# Sheet1.net
KiCad netlist of a schematic drawn in Altium Designer
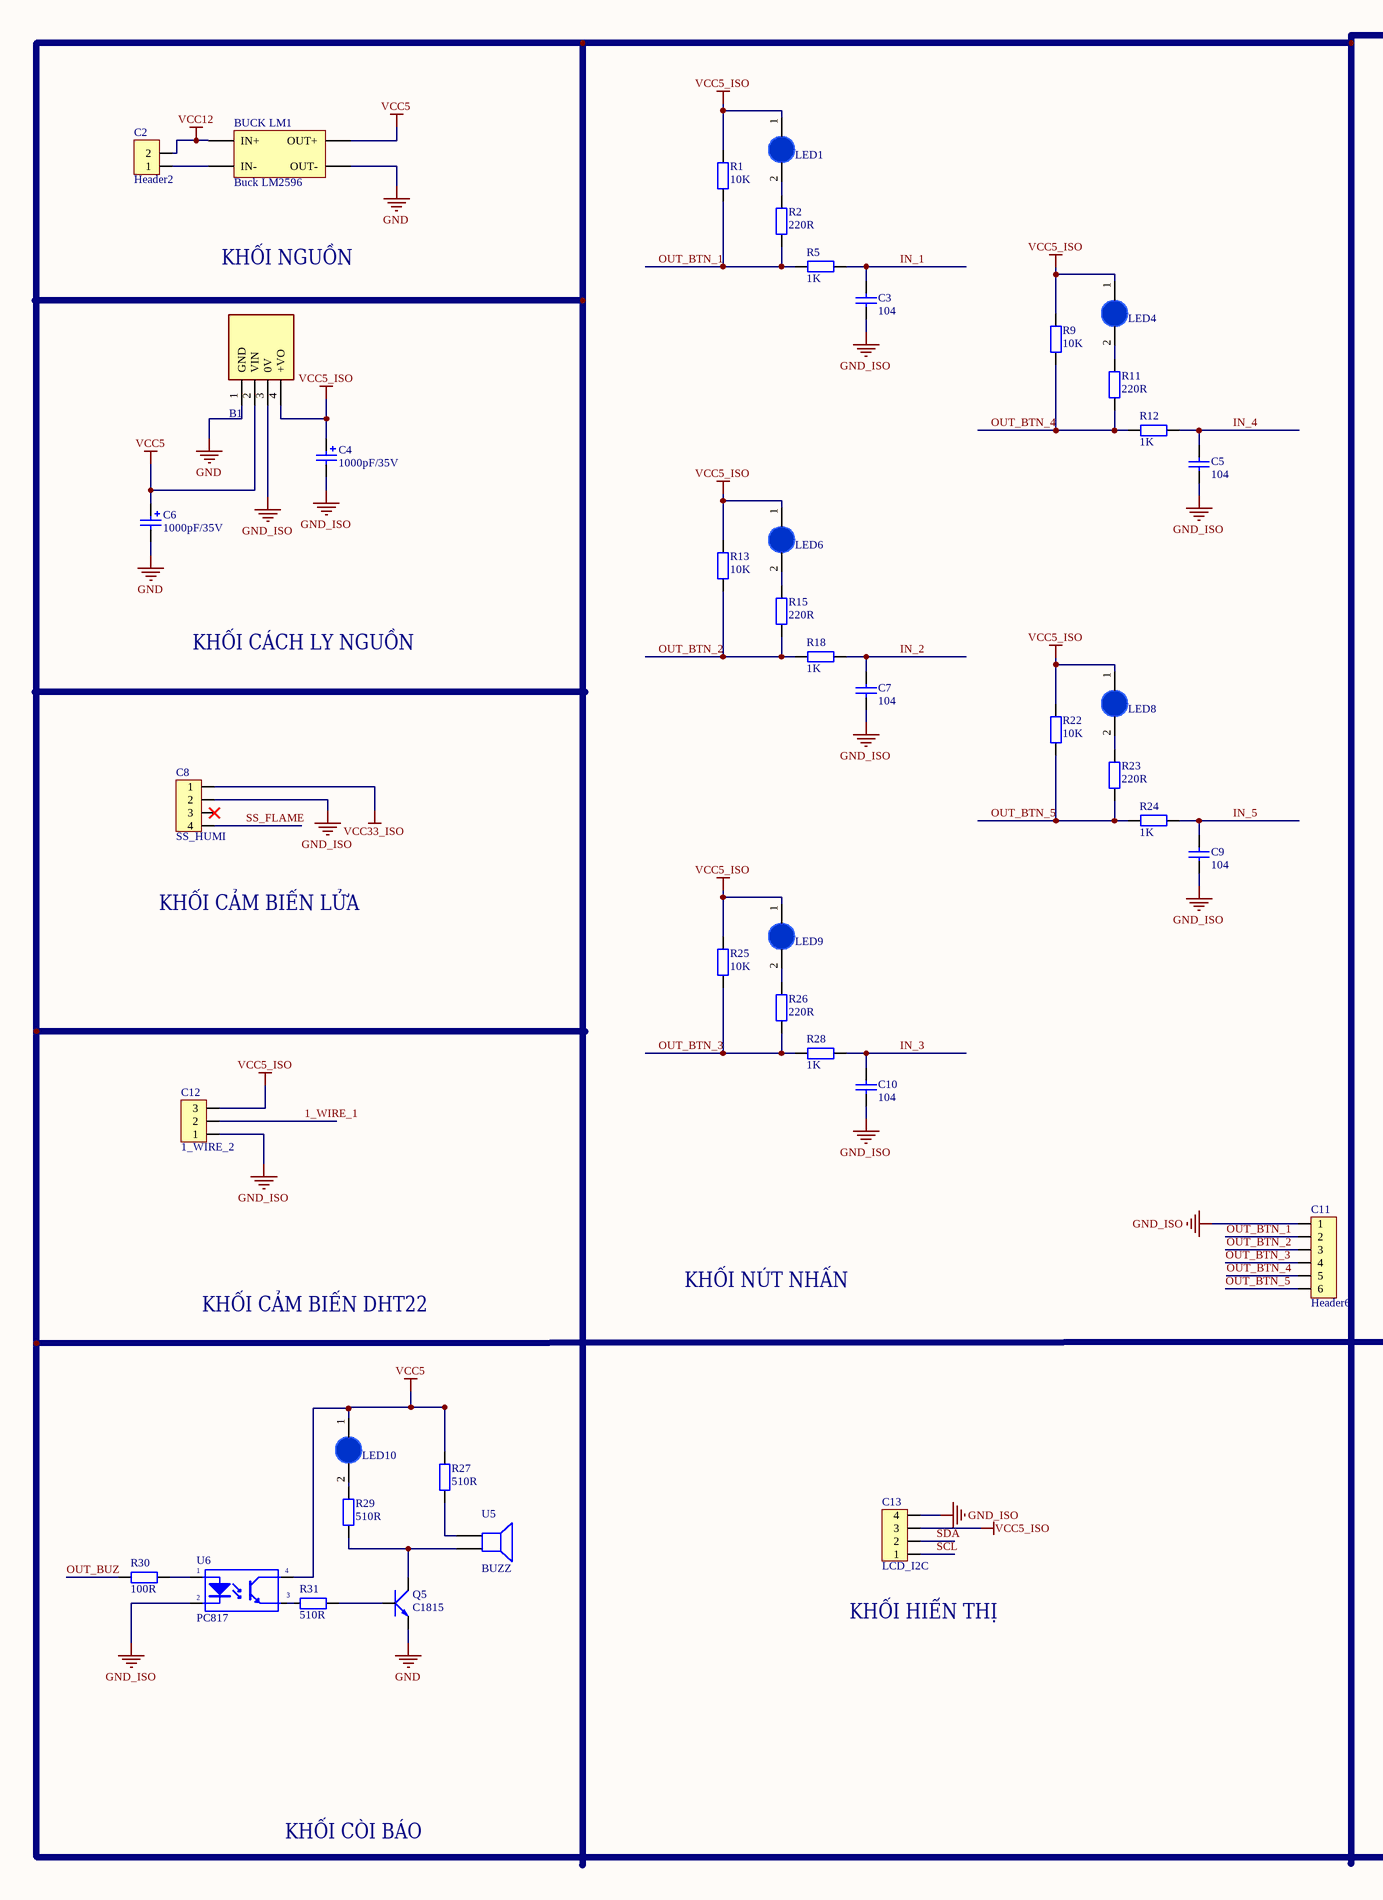
[diagram p0: Sheet1.SchDoc, left]
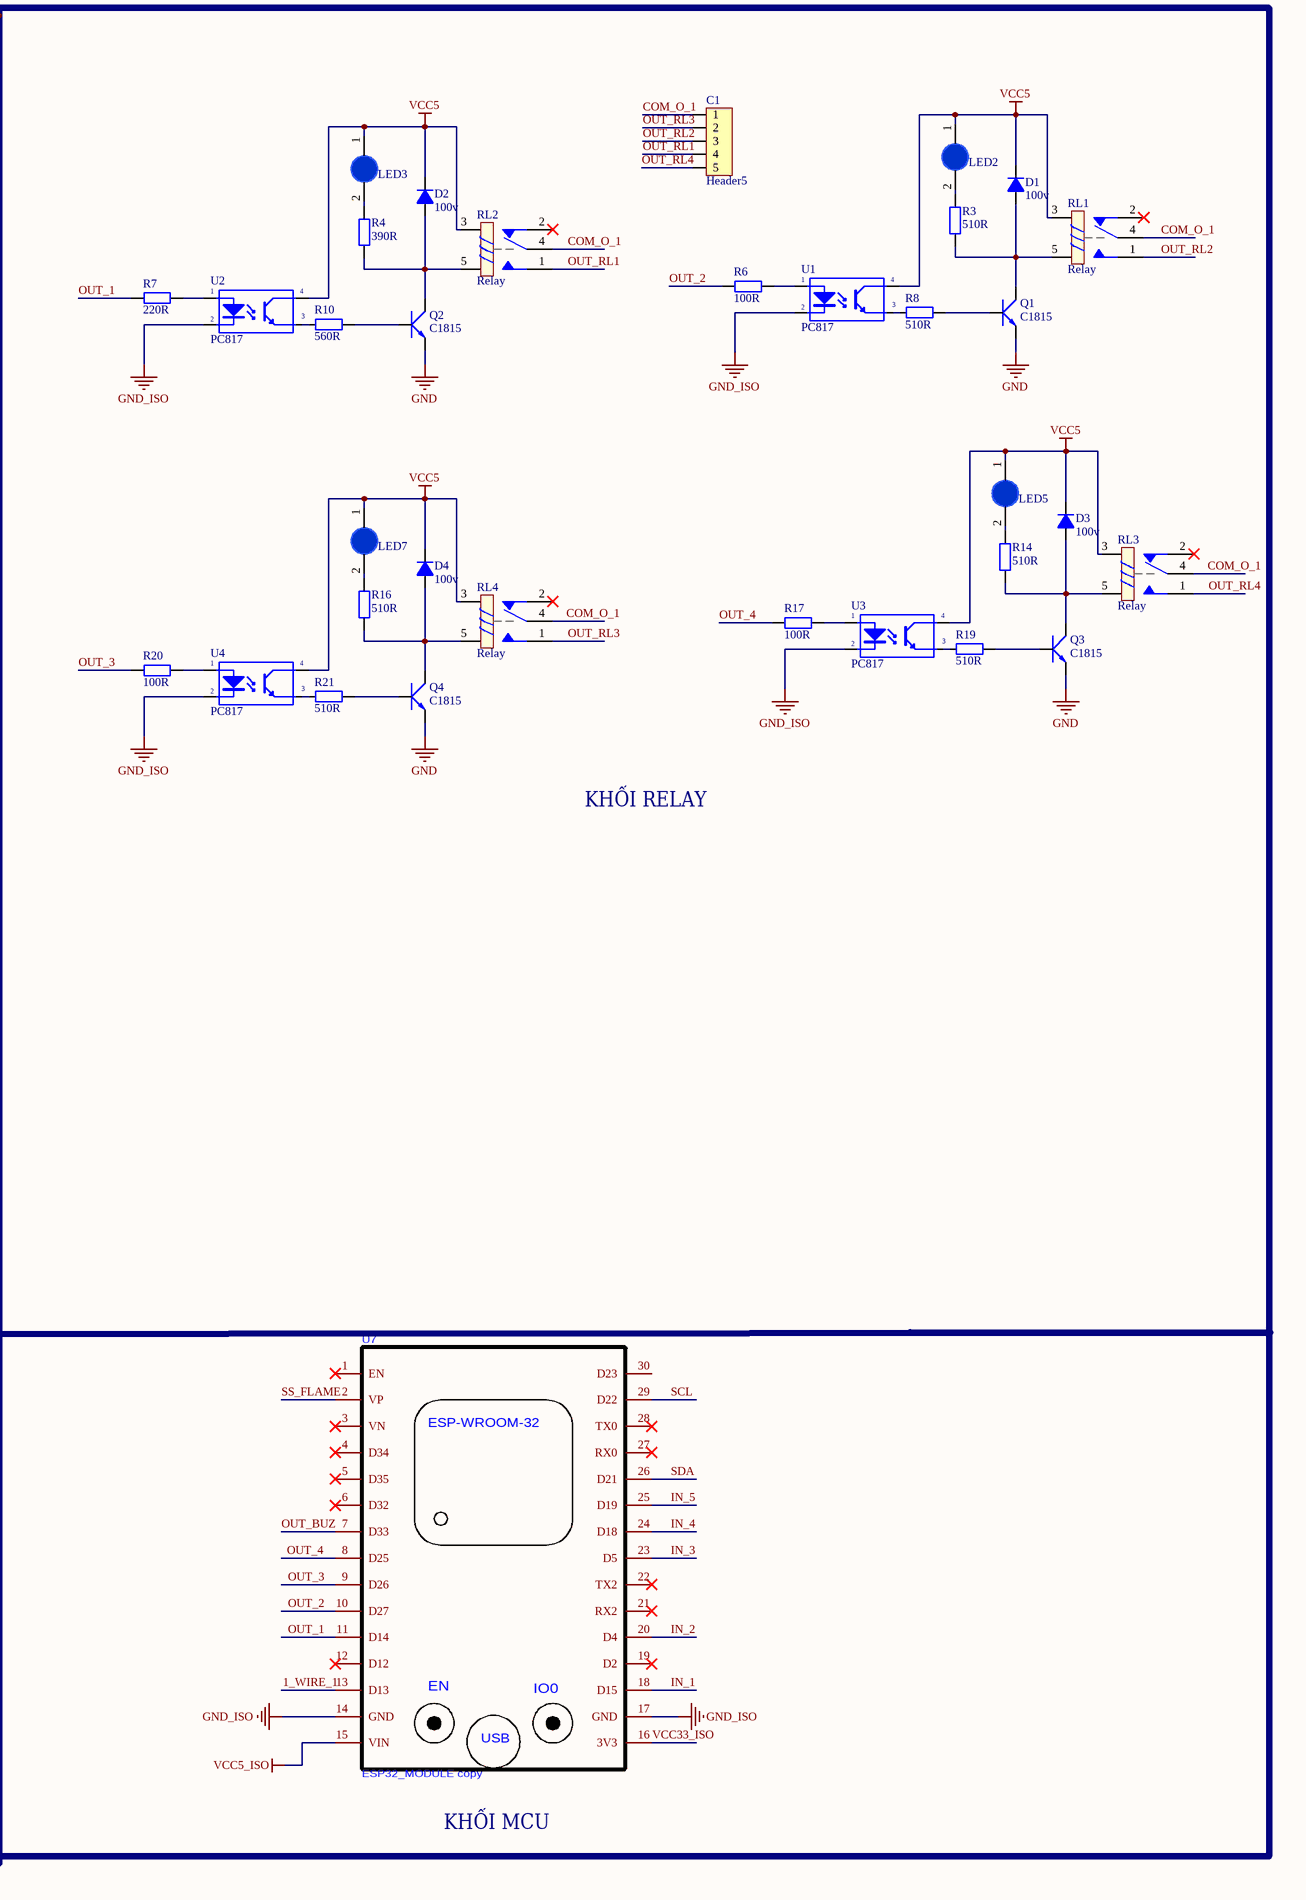
[diagram p1: Sheet1.SchDoc, right]

(export (version "E")
  (design (tool "Eeschema 10.0.6"))
  (components
    (comp (ref "B1")
      (value "B0505S1W")
      (footprint "B0505S1W")
      (description "Power Supply")
      (fields (field (name "MANUFACTURER_PART_NUMBER") "B0505S-1W"))
      (libsource (lib "myLib_v1") (part "B0505S1W"))
    )
    (comp (ref "BUCK LM1")
      (value "Buck LM2596")
      (footprint "BUCK LM2596")
      (libsource (lib "myLib_v1") (part "Buck LM2596"))
    )
    (comp (ref "C1")
      (value "Header5")
      (footprint "Header5")
      (description "Header IDC, 5 x 1 Pin Vertical 2.54mm Pitch (Non-Boxed, Male)")
      (fields
        (field (name "MANUFACTURER") "Würth Elektronik eiSos GmbH")
        (field (name "PARTNO") "613002143121")
        (field (name "CREATED BY") "Karrer Zheng")
      )
      (libsource (lib "myLib_v1") (part "Header5"))
    )
    (comp (ref "C2")
      (value "Header2")
      (footprint "Header2")
      (description "Header IDC, 2 x 1 Pin Vertical 2.54mm Pitch (Non-Boxed, Male)")
      (fields
        (field (name "MANUFACTURER") "Würth Elektronik eiSos GmbH")
        (field (name "PARTNO") "613002143121")
        (field (name "CREATED BY") "Karrer Zheng")
      )
      (libsource (lib "myLib_v1") (part "Header2"))
    )
    (comp (ref "C3")
      (value "104")
      (footprint "tu gom")
      (description "Cắm")
      (libsource (lib "Altium_Lib_by_KhueNguyenCreator") (part "Tu gom 104 50V"))
    )
    (comp (ref "C4")
      (value "1000pF/35V")
      (footprint "CP2/5")
      (description "Polarized Capacitor (Surface Mount)")
      (fields (field (name "Comment") "Cap Pol3") (field (name "PUBLISHER") "Altium Limited"))
      (libsource (lib "myLib_v1") (part "Cap Pol3"))
    )
    (comp (ref "C5")
      (value "104")
      (footprint "tu gom")
      (description "Cắm")
      (libsource (lib "Altium_Lib_by_KhueNguyenCreator") (part "Tu gom 104 50V"))
    )
    (comp (ref "C6")
      (value "1000pF/35V")
      (footprint "CP2/5")
      (description "Polarized Capacitor (Surface Mount)")
      (fields (field (name "Comment") "Cap Pol3") (field (name "PUBLISHER") "Altium Limited"))
      (libsource (lib "myLib_v1") (part "Cap Pol3"))
    )
    (comp (ref "C7")
      (value "104")
      (footprint "tu gom")
      (description "Cắm")
      (libsource (lib "Altium_Lib_by_KhueNguyenCreator") (part "Tu gom 104 50V"))
    )
    (comp (ref "C8")
      (value "SS_HUMI")
      (footprint "Header4")
      (description "Header IDC, 4 x 1 Pin Vertical 2.54mm Pitch (Non-Boxed, Male)")
      (fields
        (field (name "MANUFACTURER") "Würth Elektronik eiSos GmbH")
        (field (name "PARTNO") "613002143121")
        (field (name "CREATED BY") "Karrer Zheng")
      )
      (libsource (lib "") (part "Header4_1"))
    )
    (comp (ref "C9")
      (value "104")
      (footprint "tu gom")
      (description "Cắm")
      (libsource (lib "Altium_Lib_by_KhueNguyenCreator") (part "Tu gom 104 50V"))
    )
    (comp (ref "C10")
      (value "104")
      (footprint "tu gom")
      (description "Cắm")
      (libsource (lib "Altium_Lib_by_KhueNguyenCreator") (part "Tu gom 104 50V"))
    )
    (comp (ref "C11")
      (value "Header6")
      (footprint "HDR6")
      (description "Header IDC, 6 x 1 Pin Vertical 2.54mm Pitch (Non-Boxed, Male)")
      (fields
        (field (name "MANUFACTURER") "Würth Elektronik eiSos GmbH")
        (field (name "PARTNO") "613002143121")
        (field (name "CREATED BY") "Karrer Zheng")
      )
      (libsource (lib "myLib_v1") (part "Header6"))
    )
    (comp (ref "C12")
      (value "1_WIRE_2")
      (footprint "Header3")
      (description "Header IDC, 3 x 1 Pin Vertical 2.54mm Pitch (Non-Boxed, Male)")
      (fields
        (field (name "MANUFACTURER") "Würth Elektronik eiSos GmbH")
        (field (name "PARTNO") "613002143121")
        (field (name "CREATED BY") "Karrer Zheng")
      )
      (libsource (lib "myLib_v1") (part "Header3"))
    )
    (comp (ref "C13")
      (value "LCD_I2C")
      (footprint "Header4")
      (description "Header IDC, 4 x 1 Pin Vertical 2.54mm Pitch (Non-Boxed, Male)")
      (fields
        (field (name "MANUFACTURER") "Würth Elektronik eiSos GmbH")
        (field (name "PARTNO") "613002143121")
        (field (name "CREATED BY") "Karrer Zheng")
      )
      (libsource (lib "myLib_v1") (part "Header4"))
    )
    (comp (ref "D1")
      (value "100v")
      (footprint "DIODE 0.5A")
      (description "Cắm")
      (libsource (lib "Altium_Lib_by_KhueNguyenCreator") (part "Diode 1N4148"))
    )
    (comp (ref "D2")
      (value "100v")
      (footprint "DIODE 0.5A")
      (description "Cắm")
      (libsource (lib "Altium_Lib_by_KhueNguyenCreator") (part "Diode 1N4148"))
    )
    (comp (ref "D3")
      (value "100v")
      (footprint "DIODE 0.5A")
      (description "Cắm")
      (libsource (lib "Altium_Lib_by_KhueNguyenCreator") (part "Diode 1N4148"))
    )
    (comp (ref "D4")
      (value "100v")
      (footprint "DIODE 0.5A")
      (description "Cắm")
      (libsource (lib "Altium_Lib_by_KhueNguyenCreator") (part "Diode 1N4148"))
    )
    (comp (ref "LED1")
      (value "LED 3mm")
      (footprint "LED-3MM-BLUE")
      (description "Cắm")
      (libsource (lib "myLib_v1") (part "LED 3mm Xanh Duong"))
    )
    (comp (ref "LED2")
      (value "LED 3mm")
      (footprint "LED-3MM-BLUE")
      (description "Cắm")
      (libsource (lib "myLib_v1") (part "LED 3mm Xanh Duong"))
    )
    (comp (ref "LED3")
      (value "LED 3mm")
      (footprint "LED-3MM-BLUE")
      (description "Cắm")
      (libsource (lib "myLib_v1") (part "LED 3mm Xanh Duong"))
    )
    (comp (ref "LED4")
      (value "LED 3mm")
      (footprint "LED-3MM-BLUE")
      (description "Cắm")
      (libsource (lib "myLib_v1") (part "LED 3mm Xanh Duong"))
    )
    (comp (ref "LED5")
      (value "LED 3mm")
      (footprint "LED-3MM-BLUE")
      (description "Cắm")
      (libsource (lib "myLib_v1") (part "LED 3mm Xanh Duong"))
    )
    (comp (ref "LED6")
      (value "LED 3mm")
      (footprint "LED-3MM-BLUE")
      (description "Cắm")
      (libsource (lib "myLib_v1") (part "LED 3mm Xanh Duong"))
    )
    (comp (ref "LED7")
      (value "LED 3mm")
      (footprint "LED-3MM-BLUE")
      (description "Cắm")
      (libsource (lib "myLib_v1") (part "LED 3mm Xanh Duong"))
    )
    (comp (ref "LED8")
      (value "LED 3mm")
      (footprint "LED-3MM-BLUE")
      (description "Cắm")
      (libsource (lib "myLib_v1") (part "LED 3mm Xanh Duong"))
    )
    (comp (ref "LED9")
      (value "LED 3mm")
      (footprint "LED-3MM-BLUE")
      (description "Cắm")
      (libsource (lib "myLib_v1") (part "LED 3mm Xanh Duong"))
    )
    (comp (ref "LED10")
      (value "LED 3mm")
      (footprint "LED-3MM-BLUE")
      (description "Cắm")
      (libsource (lib "myLib_v1") (part "LED 3mm Xanh Duong"))
    )
    (comp (ref "Q1")
      (value "C1815")
      (footprint "C1815_cam")
      (description "NPN 600mW, ECB")
      (libsource (lib "myLib_v1") (part "C1815"))
    )
    (comp (ref "Q2")
      (value "C1815")
      (footprint "C1815_cam")
      (description "NPN 600mW, ECB")
      (libsource (lib "myLib_v1") (part "C1815"))
    )
    (comp (ref "Q3")
      (value "C1815")
      (footprint "C1815_cam")
      (description "NPN 600mW, ECB")
      (libsource (lib "myLib_v1") (part "C1815"))
    )
    (comp (ref "Q4")
      (value "C1815")
      (footprint "C1815_cam")
      (description "NPN 600mW, ECB")
      (libsource (lib "myLib_v1") (part "C1815"))
    )
    (comp (ref "Q5")
      (value "C1815")
      (footprint "C1815_cam")
      (description "NPN 600mW, ECB")
      (libsource (lib "myLib_v1") (part "C1815"))
    )
    (comp (ref "R1")
      (value "10K")
      (footprint "R1/4W")
      (description "Resistor 1/4W")
      (libsource (lib "myLib_v1") (part "R1/4W"))
    )
    (comp (ref "R2")
      (value "220R")
      (footprint "R1/4W")
      (description "Resistor 1/4W")
      (libsource (lib "myLib_v1") (part "R1/4W"))
    )
    (comp (ref "R3")
      (value "510R")
      (footprint "R1/4W")
      (description "Resistor 1/4W")
      (libsource (lib "myLib_v1") (part "R1/4W"))
    )
    (comp (ref "R4")
      (value "390R")
      (footprint "R1/4W")
      (description "Resistor 1/4W")
      (libsource (lib "myLib_v1") (part "R1/4W"))
    )
    (comp (ref "R5")
      (value "1K")
      (footprint "R1/4W")
      (description "Resistor 1/4W")
      (libsource (lib "myLib_v1") (part "R1/4W"))
    )
    (comp (ref "R6")
      (value "100R")
      (footprint "R1/4W")
      (description "Resistor 1/4W")
      (libsource (lib "myLib_v1") (part "R1/4W"))
    )
    (comp (ref "R7")
      (value "220R")
      (footprint "R1/4W")
      (description "Resistor 1/4W")
      (libsource (lib "myLib_v1") (part "R1/4W"))
    )
    (comp (ref "R8")
      (value "510R")
      (footprint "R1/4W")
      (description "Resistor 1/4W")
      (libsource (lib "myLib_v1") (part "R1/4W"))
    )
    (comp (ref "R9")
      (value "10K")
      (footprint "R1/4W")
      (description "Resistor 1/4W")
      (libsource (lib "myLib_v1") (part "R1/4W"))
    )
    (comp (ref "R10")
      (value "560R")
      (footprint "R1/4W")
      (description "Resistor 1/4W")
      (libsource (lib "myLib_v1") (part "R1/4W"))
    )
    (comp (ref "R11")
      (value "220R")
      (footprint "R1/4W")
      (description "Resistor 1/4W")
      (libsource (lib "myLib_v1") (part "R1/4W"))
    )
    (comp (ref "R12")
      (value "1K")
      (footprint "R1/4W")
      (description "Resistor 1/4W")
      (libsource (lib "myLib_v1") (part "R1/4W"))
    )
    (comp (ref "R13")
      (value "10K")
      (footprint "R1/4W")
      (description "Resistor 1/4W")
      (libsource (lib "myLib_v1") (part "R1/4W"))
    )
    (comp (ref "R14")
      (value "510R")
      (footprint "R1/4W")
      (description "Resistor 1/4W")
      (libsource (lib "myLib_v1") (part "R1/4W"))
    )
    (comp (ref "R15")
      (value "220R")
      (footprint "R1/4W")
      (description "Resistor 1/4W")
      (libsource (lib "myLib_v1") (part "R1/4W"))
    )
    (comp (ref "R16")
      (value "510R")
      (footprint "R1/4W")
      (description "Resistor 1/4W")
      (libsource (lib "myLib_v1") (part "R1/4W"))
    )
    (comp (ref "R17")
      (value "100R")
      (footprint "R1/4W")
      (description "Resistor 1/4W")
      (libsource (lib "myLib_v1") (part "R1/4W"))
    )
    (comp (ref "R18")
      (value "1K")
      (footprint "R1/4W")
      (description "Resistor 1/4W")
      (libsource (lib "myLib_v1") (part "R1/4W"))
    )
    (comp (ref "R19")
      (value "510R")
      (footprint "R1/4W")
      (description "Resistor 1/4W")
      (libsource (lib "myLib_v1") (part "R1/4W"))
    )
    (comp (ref "R20")
      (value "100R")
      (footprint "R1/4W")
      (description "Resistor 1/4W")
      (libsource (lib "myLib_v1") (part "R1/4W"))
    )
    (comp (ref "R21")
      (value "510R")
      (footprint "R1/4W")
      (description "Resistor 1/4W")
      (libsource (lib "myLib_v1") (part "R1/4W"))
    )
    (comp (ref "R22")
      (value "10K")
      (footprint "R1/4W")
      (description "Resistor 1/4W")
      (libsource (lib "myLib_v1") (part "R1/4W"))
    )
    (comp (ref "R23")
      (value "220R")
      (footprint "R1/4W")
      (description "Resistor 1/4W")
      (libsource (lib "myLib_v1") (part "R1/4W"))
    )
    (comp (ref "R24")
      (value "1K")
      (footprint "R1/4W")
      (description "Resistor 1/4W")
      (libsource (lib "myLib_v1") (part "R1/4W"))
    )
    (comp (ref "R25")
      (value "10K")
      (footprint "R1/4W")
      (description "Resistor 1/4W")
      (libsource (lib "myLib_v1") (part "R1/4W"))
    )
    (comp (ref "R26")
      (value "220R")
      (footprint "R1/4W")
      (description "Resistor 1/4W")
      (libsource (lib "myLib_v1") (part "R1/4W"))
    )
    (comp (ref "R27")
      (value "510R")
      (footprint "R1/4W")
      (description "Resistor 1/4W")
      (libsource (lib "myLib_v1") (part "R1/4W"))
    )
    (comp (ref "R28")
      (value "1K")
      (footprint "R1/4W")
      (description "Resistor 1/4W")
      (libsource (lib "myLib_v1") (part "R1/4W"))
    )
    (comp (ref "R29")
      (value "510R")
      (footprint "R1/4W")
      (description "Resistor 1/4W")
      (libsource (lib "myLib_v1") (part "R1/4W"))
    )
    (comp (ref "R30")
      (value "100R")
      (footprint "R1/4W")
      (description "Resistor 1/4W")
      (libsource (lib "myLib_v1") (part "R1/4W"))
    )
    (comp (ref "R31")
      (value "510R")
      (footprint "R1/4W")
      (description "Resistor 1/4W")
      (libsource (lib "myLib_v1") (part "R1/4W"))
    )
    (comp (ref "RL1")
      (value "Relay")
      (footprint "RELAY_SRA_05VDC_SL_C")
      (description "Relay 5 Chan")
      (libsource (lib "myLib_v1") (part "RL_SRA-05VDC-SL-C"))
    )
    (comp (ref "RL2")
      (value "Relay")
      (footprint "RELAY_SRA_05VDC_SL_C")
      (description "Relay 5 Chan")
      (libsource (lib "myLib_v1") (part "RL_SRA-05VDC-SL-C"))
    )
    (comp (ref "RL3")
      (value "Relay")
      (footprint "RELAY_SRA_05VDC_SL_C")
      (description "Relay 5 Chan")
      (libsource (lib "myLib_v1") (part "RL_SRA-05VDC-SL-C"))
    )
    (comp (ref "RL4")
      (value "Relay")
      (footprint "RELAY_SRA_05VDC_SL_C")
      (description "Relay 5 Chan")
      (libsource (lib "myLib_v1") (part "RL_SRA-05VDC-SL-C"))
    )
    (comp (ref "U1")
      (value "PC817")
      (footprint "DIP4/W0.3")
      (description "Single Opto")
      (libsource (lib "myLib_v1") (part "PC817"))
    )
    (comp (ref "U2")
      (value "PC817")
      (footprint "DIP4/W0.3")
      (description "Single Opto")
      (libsource (lib "myLib_v1") (part "PC817"))
    )
    (comp (ref "U3")
      (value "PC817")
      (footprint "DIP4/W0.3")
      (description "Single Opto")
      (libsource (lib "myLib_v1") (part "PC817"))
    )
    (comp (ref "U4")
      (value "PC817")
      (footprint "DIP4/W0.3")
      (description "Single Opto")
      (libsource (lib "myLib_v1") (part "PC817"))
    )
    (comp (ref "U5")
      (value "BUZZ")
      (footprint "BUZZER_D9_TH")
      (description "Loudspeaker")
      (libsource (lib "BYTECH_HW_LIB_2019 (1)") (part "Speaker"))
    )
    (comp (ref "U6")
      (value "PC817")
      (footprint "DIP4/W0.3")
      (description "Single Opto")
      (libsource (lib "myLib_v1") (part "PC817"))
    )
    (comp (ref "U7")
      (value "ESP32_MODULE copy")
      (footprint "ESP32-WIFIMODULE-FOOTPRINT")
      (libsource (lib "myLib_v1") (part "ESP32_MODULE copy"))
    )
  )
  (nets
    (net (code "1") (name "/1_WIRE_1") (class "Default")
      (node (ref "C12") (pin "2") (pinfunction "2_2") (pintype "passive"))
      (node (ref "U7") (pin "13") (pinfunction "D13_13") (pintype "passive"))
    )
    (net (code "2") (name "/COM_O_1") (class "Default")
      (node (ref "C1") (pin "1") (pinfunction "1_1") (pintype "passive"))
      (node (ref "RL1") (pin "4") (pinfunction "4_4") (pintype "passive"))
      (node (ref "RL2") (pin "4") (pinfunction "4_4") (pintype "passive"))
      (node (ref "RL3") (pin "4") (pinfunction "4_4") (pintype "passive"))
      (node (ref "RL4") (pin "4") (pinfunction "4_4") (pintype "passive"))
    )
    (net (code "3") (name "/IN_1") (class "Default")
      (node (ref "C3") (pin "1") (pinfunction "1_1") (pintype "passive"))
      (node (ref "R5") (pin "1") (pinfunction "1_1") (pintype "passive"))
      (node (ref "U7") (pin "18") (pinfunction "D15_18") (pintype "passive"))
    )
    (net (code "4") (name "/IN_2") (class "Default")
      (node (ref "C7") (pin "1") (pinfunction "1_1") (pintype "passive"))
      (node (ref "R18") (pin "1") (pinfunction "1_1") (pintype "passive"))
      (node (ref "U7") (pin "20") (pinfunction "D4_20") (pintype "passive"))
    )
    (net (code "5") (name "/IN_3") (class "Default")
      (node (ref "C10") (pin "1") (pinfunction "1_1") (pintype "passive"))
      (node (ref "R28") (pin "1") (pinfunction "1_1") (pintype "passive"))
      (node (ref "U7") (pin "23") (pinfunction "D5_23") (pintype "passive"))
    )
    (net (code "6") (name "/IN_4") (class "Default")
      (node (ref "C5") (pin "1") (pinfunction "1_1") (pintype "passive"))
      (node (ref "R12") (pin "1") (pinfunction "1_1") (pintype "passive"))
      (node (ref "U7") (pin "24") (pinfunction "D18_24") (pintype "passive"))
    )
    (net (code "7") (name "/IN_5") (class "Default")
      (node (ref "C9") (pin "1") (pinfunction "1_1") (pintype "passive"))
      (node (ref "R24") (pin "1") (pinfunction "1_1") (pintype "passive"))
      (node (ref "U7") (pin "25") (pinfunction "D19_25") (pintype "passive"))
    )
    (net (code "8") (name "/OUT_1") (class "Default")
      (node (ref "R7") (pin "1") (pinfunction "1_1") (pintype "passive"))
      (node (ref "U7") (pin "11") (pinfunction "D14_11") (pintype "passive"))
    )
    (net (code "9") (name "/OUT_2") (class "Default")
      (node (ref "R6") (pin "1") (pinfunction "1_1") (pintype "passive"))
      (node (ref "U7") (pin "10") (pinfunction "D27_10") (pintype "passive"))
    )
    (net (code "10") (name "/OUT_3") (class "Default")
      (node (ref "R20") (pin "1") (pinfunction "1_1") (pintype "passive"))
      (node (ref "U7") (pin "9") (pinfunction "D26_9") (pintype "passive"))
    )
    (net (code "11") (name "/OUT_4") (class "Default")
      (node (ref "R17") (pin "1") (pinfunction "1_1") (pintype "passive"))
      (node (ref "U7") (pin "8") (pinfunction "D25_8") (pintype "passive"))
    )
    (net (code "12") (name "/OUT_BTN_1") (class "Default")
      (node (ref "C11") (pin "2") (pinfunction "2_2") (pintype "passive"))
      (node (ref "R1") (pin "1") (pinfunction "1_1") (pintype "passive"))
      (node (ref "R2") (pin "1") (pinfunction "1_1") (pintype "passive"))
      (node (ref "R5") (pin "2") (pinfunction "2_2") (pintype "passive"))
    )
    (net (code "13") (name "/OUT_BTN_2") (class "Default")
      (node (ref "C11") (pin "3") (pinfunction "3_3") (pintype "passive"))
      (node (ref "R13") (pin "1") (pinfunction "1_1") (pintype "passive"))
      (node (ref "R15") (pin "1") (pinfunction "1_1") (pintype "passive"))
      (node (ref "R18") (pin "2") (pinfunction "2_2") (pintype "passive"))
    )
    (net (code "14") (name "/OUT_BTN_3") (class "Default")
      (node (ref "C11") (pin "4") (pinfunction "4_4") (pintype "passive"))
      (node (ref "R25") (pin "1") (pinfunction "1_1") (pintype "passive"))
      (node (ref "R26") (pin "1") (pinfunction "1_1") (pintype "passive"))
      (node (ref "R28") (pin "2") (pinfunction "2_2") (pintype "passive"))
    )
    (net (code "15") (name "/OUT_BTN_4") (class "Default")
      (node (ref "C11") (pin "5") (pinfunction "5_5") (pintype "passive"))
      (node (ref "R11") (pin "1") (pinfunction "1_1") (pintype "passive"))
      (node (ref "R12") (pin "2") (pinfunction "2_2") (pintype "passive"))
      (node (ref "R9") (pin "1") (pinfunction "1_1") (pintype "passive"))
    )
    (net (code "16") (name "/OUT_BTN_5") (class "Default")
      (node (ref "C11") (pin "6") (pinfunction "6_6") (pintype "passive"))
      (node (ref "R22") (pin "1") (pinfunction "1_1") (pintype "passive"))
      (node (ref "R23") (pin "1") (pinfunction "1_1") (pintype "passive"))
      (node (ref "R24") (pin "2") (pinfunction "2_2") (pintype "passive"))
    )
    (net (code "17") (name "/OUT_BUZ") (class "Default")
      (node (ref "R30") (pin "1") (pinfunction "1_1") (pintype "passive"))
      (node (ref "U7") (pin "7") (pinfunction "D33_7") (pintype "passive"))
    )
    (net (code "18") (name "/OUT_RL1") (class "Default")
      (node (ref "C1") (pin "4") (pinfunction "4_4") (pintype "passive"))
      (node (ref "RL2") (pin "1") (pinfunction "1_1") (pintype "passive"))
    )
    (net (code "19") (name "/OUT_RL2") (class "Default")
      (node (ref "C1") (pin "3") (pinfunction "3_3") (pintype "passive"))
      (node (ref "RL1") (pin "1") (pinfunction "1_1") (pintype "passive"))
    )
    (net (code "20") (name "/OUT_RL3") (class "Default")
      (node (ref "C1") (pin "2") (pinfunction "2_2") (pintype "passive"))
      (node (ref "RL4") (pin "1") (pinfunction "1_1") (pintype "passive"))
    )
    (net (code "21") (name "/OUT_RL4") (class "Default")
      (node (ref "C1") (pin "5") (pinfunction "5_5") (pintype "passive"))
      (node (ref "RL3") (pin "1") (pinfunction "1_1") (pintype "passive"))
    )
    (net (code "22") (name "/SCL") (class "Default")
      (node (ref "C13") (pin "1") (pinfunction "1_1") (pintype "passive"))
      (node (ref "U7") (pin "29") (pinfunction "D22_29") (pintype "passive"))
    )
    (net (code "23") (name "/SDA") (class "Default")
      (node (ref "C13") (pin "2") (pinfunction "2_2") (pintype "passive"))
      (node (ref "U7") (pin "26") (pinfunction "D21_26") (pintype "passive"))
    )
    (net (code "24") (name "/SS_FLAME") (class "Default")
      (node (ref "C8") (pin "4") (pinfunction "4_4") (pintype "passive"))
      (node (ref "U7") (pin "2") (pinfunction "VP_2") (pintype "passive"))
    )
    (net (code "25") (name "GND") (class "Default")
      (node (ref "B1") (pin "1") (pinfunction "GND_1") (pintype "passive"))
      (node (ref "BUCK LM1") (pin "3") (pinfunction "OUT-_3") (pintype "passive"))
      (node (ref "C6") (pin "2") (pinfunction "2_2") (pintype "passive"))
      (node (ref "Q1") (pin "1") (pinfunction "E_1") (pintype "passive"))
      (node (ref "Q2") (pin "1") (pinfunction "E_1") (pintype "passive"))
      (node (ref "Q3") (pin "1") (pinfunction "E_1") (pintype "passive"))
      (node (ref "Q4") (pin "1") (pinfunction "E_1") (pintype "passive"))
      (node (ref "Q5") (pin "1") (pinfunction "E_1") (pintype "passive"))
    )
    (net (code "26") (name "GND_ISO") (class "Default")
      (node (ref "B1") (pin "3") (pinfunction "0V_3") (pintype "passive"))
      (node (ref "C10") (pin "2") (pinfunction "2_2") (pintype "passive"))
      (node (ref "C11") (pin "1") (pinfunction "1_1") (pintype "passive"))
      (node (ref "C12") (pin "1") (pinfunction "1_1") (pintype "passive"))
      (node (ref "C13") (pin "4") (pinfunction "4_4") (pintype "passive"))
      (node (ref "C3") (pin "2") (pinfunction "2_2") (pintype "passive"))
      (node (ref "C4") (pin "2") (pinfunction "2_2") (pintype "passive"))
      (node (ref "C5") (pin "2") (pinfunction "2_2") (pintype "passive"))
      (node (ref "C7") (pin "2") (pinfunction "2_2") (pintype "passive"))
      (node (ref "C8") (pin "2") (pinfunction "2_2") (pintype "passive"))
      (node (ref "C9") (pin "2") (pinfunction "2_2") (pintype "passive"))
      (node (ref "U1") (pin "2") (pinfunction "K_2") (pintype "passive"))
      (node (ref "U2") (pin "2") (pinfunction "K_2") (pintype "passive"))
      (node (ref "U3") (pin "2") (pinfunction "K_2") (pintype "passive"))
      (node (ref "U4") (pin "2") (pinfunction "K_2") (pintype "passive"))
      (node (ref "U6") (pin "2") (pinfunction "K_2") (pintype "passive"))
      (node (ref "U7") (pin "14") (pinfunction "GND_14") (pintype "passive"))
      (node (ref "U7") (pin "17") (pinfunction "GND_17") (pintype "passive"))
    )
    (net (code "27") (name "Net-(BUCK LM1-IN-)") (class "Default")
      (node (ref "BUCK LM1") (pin "2") (pinfunction "IN-_2") (pintype "passive"))
      (node (ref "C2") (pin "1") (pinfunction "1_1") (pintype "passive"))
    )
    (net (code "28") (name "Net-(D1-A)") (class "Default")
      (node (ref "D1") (pin "1") (pinfunction "A_1") (pintype "passive"))
      (node (ref "Q1") (pin "2") (pinfunction "C_2") (pintype "passive"))
      (node (ref "R3") (pin "2") (pinfunction "2_2") (pintype "passive"))
      (node (ref "RL1") (pin "5") (pinfunction "5_5") (pintype "passive"))
    )
    (net (code "29") (name "Net-(D2-A)") (class "Default")
      (node (ref "D2") (pin "1") (pinfunction "A_1") (pintype "passive"))
      (node (ref "Q2") (pin "2") (pinfunction "C_2") (pintype "passive"))
      (node (ref "R4") (pin "2") (pinfunction "2_2") (pintype "passive"))
      (node (ref "RL2") (pin "5") (pinfunction "5_5") (pintype "passive"))
    )
    (net (code "30") (name "Net-(D3-A)") (class "Default")
      (node (ref "D3") (pin "1") (pinfunction "A_1") (pintype "passive"))
      (node (ref "Q3") (pin "2") (pinfunction "C_2") (pintype "passive"))
      (node (ref "R14") (pin "2") (pinfunction "2_2") (pintype "passive"))
      (node (ref "RL3") (pin "5") (pinfunction "5_5") (pintype "passive"))
    )
    (net (code "31") (name "Net-(D4-A)") (class "Default")
      (node (ref "D4") (pin "1") (pinfunction "A_1") (pintype "passive"))
      (node (ref "Q4") (pin "2") (pinfunction "C_2") (pintype "passive"))
      (node (ref "R16") (pin "2") (pinfunction "2_2") (pintype "passive"))
      (node (ref "RL4") (pin "5") (pinfunction "5_5") (pintype "passive"))
    )
    (net (code "32") (name "Net-(LED1-K)") (class "Default")
      (node (ref "LED1") (pin "2") (pinfunction "K_2") (pintype "passive"))
      (node (ref "R2") (pin "2") (pinfunction "2_2") (pintype "passive"))
    )
    (net (code "33") (name "Net-(LED2-K)") (class "Default")
      (node (ref "LED2") (pin "2") (pinfunction "K_2") (pintype "passive"))
      (node (ref "R3") (pin "1") (pinfunction "1_1") (pintype "passive"))
    )
    (net (code "34") (name "Net-(LED3-K)") (class "Default")
      (node (ref "LED3") (pin "2") (pinfunction "K_2") (pintype "passive"))
      (node (ref "R4") (pin "1") (pinfunction "1_1") (pintype "passive"))
    )
    (net (code "35") (name "Net-(LED4-K)") (class "Default")
      (node (ref "LED4") (pin "2") (pinfunction "K_2") (pintype "passive"))
      (node (ref "R11") (pin "2") (pinfunction "2_2") (pintype "passive"))
    )
    (net (code "36") (name "Net-(LED5-K)") (class "Default")
      (node (ref "LED5") (pin "2") (pinfunction "K_2") (pintype "passive"))
      (node (ref "R14") (pin "1") (pinfunction "1_1") (pintype "passive"))
    )
    (net (code "37") (name "Net-(LED6-K)") (class "Default")
      (node (ref "LED6") (pin "2") (pinfunction "K_2") (pintype "passive"))
      (node (ref "R15") (pin "2") (pinfunction "2_2") (pintype "passive"))
    )
    (net (code "38") (name "Net-(LED7-K)") (class "Default")
      (node (ref "LED7") (pin "2") (pinfunction "K_2") (pintype "passive"))
      (node (ref "R16") (pin "1") (pinfunction "1_1") (pintype "passive"))
    )
    (net (code "39") (name "Net-(LED8-K)") (class "Default")
      (node (ref "LED8") (pin "2") (pinfunction "K_2") (pintype "passive"))
      (node (ref "R23") (pin "2") (pinfunction "2_2") (pintype "passive"))
    )
    (net (code "40") (name "Net-(LED9-K)") (class "Default")
      (node (ref "LED9") (pin "2") (pinfunction "K_2") (pintype "passive"))
      (node (ref "R26") (pin "2") (pinfunction "2_2") (pintype "passive"))
    )
    (net (code "41") (name "Net-(LED10-K)") (class "Default")
      (node (ref "LED10") (pin "2") (pinfunction "K_2") (pintype "passive"))
      (node (ref "R29") (pin "1") (pinfunction "1_1") (pintype "passive"))
    )
    (net (code "42") (name "Net-(Q1-B)") (class "Default")
      (node (ref "Q1") (pin "3") (pinfunction "B_3") (pintype "passive"))
      (node (ref "R8") (pin "2") (pinfunction "2_2") (pintype "passive"))
    )
    (net (code "43") (name "Net-(Q2-B)") (class "Default")
      (node (ref "Q2") (pin "3") (pinfunction "B_3") (pintype "passive"))
      (node (ref "R10") (pin "2") (pinfunction "2_2") (pintype "passive"))
    )
    (net (code "44") (name "Net-(Q3-B)") (class "Default")
      (node (ref "Q3") (pin "3") (pinfunction "B_3") (pintype "passive"))
      (node (ref "R19") (pin "2") (pinfunction "2_2") (pintype "passive"))
    )
    (net (code "45") (name "Net-(Q4-B)") (class "Default")
      (node (ref "Q4") (pin "3") (pinfunction "B_3") (pintype "passive"))
      (node (ref "R21") (pin "2") (pinfunction "2_2") (pintype "passive"))
    )
    (net (code "46") (name "Net-(Q5-B)") (class "Default")
      (node (ref "Q5") (pin "3") (pinfunction "B_3") (pintype "passive"))
      (node (ref "R31") (pin "2") (pinfunction "2_2") (pintype "passive"))
    )
    (net (code "47") (name "Net-(Q5-C)") (class "Default")
      (node (ref "Q5") (pin "2") (pinfunction "C_2") (pintype "passive"))
      (node (ref "R29") (pin "2") (pinfunction "2_2") (pintype "passive"))
      (node (ref "U5") (pin "2") (pinfunction "2_2") (pintype "passive"))
    )
    (net (code "48") (name "Net-(R27-Pad2)") (class "Default")
      (node (ref "R27") (pin "2") (pinfunction "2_2") (pintype "passive"))
      (node (ref "U5") (pin "1") (pinfunction "1_1") (pintype "passive"))
    )
    (net (code "49") (name "Net-(U1-A)") (class "Default")
      (node (ref "R6") (pin "2") (pinfunction "2_2") (pintype "passive"))
      (node (ref "U1") (pin "1") (pinfunction "A_1") (pintype "passive"))
    )
    (net (code "50") (name "Net-(U1-E)") (class "Default")
      (node (ref "R8") (pin "1") (pinfunction "1_1") (pintype "passive"))
      (node (ref "U1") (pin "3") (pinfunction "E_3") (pintype "passive"))
    )
    (net (code "51") (name "Net-(U2-A)") (class "Default")
      (node (ref "R7") (pin "2") (pinfunction "2_2") (pintype "passive"))
      (node (ref "U2") (pin "1") (pinfunction "A_1") (pintype "passive"))
    )
    (net (code "52") (name "Net-(U2-E)") (class "Default")
      (node (ref "R10") (pin "1") (pinfunction "1_1") (pintype "passive"))
      (node (ref "U2") (pin "3") (pinfunction "E_3") (pintype "passive"))
    )
    (net (code "53") (name "Net-(U3-A)") (class "Default")
      (node (ref "R17") (pin "2") (pinfunction "2_2") (pintype "passive"))
      (node (ref "U3") (pin "1") (pinfunction "A_1") (pintype "passive"))
    )
    (net (code "54") (name "Net-(U3-E)") (class "Default")
      (node (ref "R19") (pin "1") (pinfunction "1_1") (pintype "passive"))
      (node (ref "U3") (pin "3") (pinfunction "E_3") (pintype "passive"))
    )
    (net (code "55") (name "Net-(U4-A)") (class "Default")
      (node (ref "R20") (pin "2") (pinfunction "2_2") (pintype "passive"))
      (node (ref "U4") (pin "1") (pinfunction "A_1") (pintype "passive"))
    )
    (net (code "56") (name "Net-(U4-E)") (class "Default")
      (node (ref "R21") (pin "1") (pinfunction "1_1") (pintype "passive"))
      (node (ref "U4") (pin "3") (pinfunction "E_3") (pintype "passive"))
    )
    (net (code "57") (name "Net-(U6-A)") (class "Default")
      (node (ref "R30") (pin "2") (pinfunction "2_2") (pintype "passive"))
      (node (ref "U6") (pin "1") (pinfunction "A_1") (pintype "passive"))
    )
    (net (code "58") (name "Net-(U6-E)") (class "Default")
      (node (ref "R31") (pin "1") (pinfunction "1_1") (pintype "passive"))
      (node (ref "U6") (pin "3") (pinfunction "E_3") (pintype "passive"))
    )
    (net (code "59") (name "VCC5") (class "Default")
      (node (ref "B1") (pin "2") (pinfunction "VIN_2") (pintype "passive"))
      (node (ref "BUCK LM1") (pin "4") (pinfunction "OUT+_4") (pintype "passive"))
      (node (ref "C6") (pin "1") (pinfunction "1_1") (pintype "passive"))
      (node (ref "D1") (pin "2") (pinfunction "K_2") (pintype "passive"))
      (node (ref "D2") (pin "2") (pinfunction "K_2") (pintype "passive"))
      (node (ref "D3") (pin "2") (pinfunction "K_2") (pintype "passive"))
      (node (ref "D4") (pin "2") (pinfunction "K_2") (pintype "passive"))
      (node (ref "LED10") (pin "1") (pinfunction "A_1") (pintype "passive"))
      (node (ref "LED2") (pin "1") (pinfunction "A_1") (pintype "passive"))
      (node (ref "LED3") (pin "1") (pinfunction "A_1") (pintype "passive"))
      (node (ref "LED5") (pin "1") (pinfunction "A_1") (pintype "passive"))
      (node (ref "LED7") (pin "1") (pinfunction "A_1") (pintype "passive"))
      (node (ref "R27") (pin "1") (pinfunction "1_1") (pintype "passive"))
      (node (ref "RL1") (pin "3") (pinfunction "3_3") (pintype "passive"))
      (node (ref "RL2") (pin "3") (pinfunction "3_3") (pintype "passive"))
      (node (ref "RL3") (pin "3") (pinfunction "3_3") (pintype "passive"))
      (node (ref "RL4") (pin "3") (pinfunction "3_3") (pintype "passive"))
      (node (ref "U1") (pin "4") (pinfunction "C_4") (pintype "passive"))
      (node (ref "U2") (pin "4") (pinfunction "C_4") (pintype "passive"))
      (node (ref "U3") (pin "4") (pinfunction "C_4") (pintype "passive"))
      (node (ref "U4") (pin "4") (pinfunction "C_4") (pintype "passive"))
      (node (ref "U6") (pin "4") (pinfunction "C_4") (pintype "passive"))
    )
    (net (code "60") (name "VCC5_ISO") (class "Default")
      (node (ref "B1") (pin "4") (pinfunction "+VO_4") (pintype "passive"))
      (node (ref "C12") (pin "3") (pinfunction "3_3") (pintype "passive"))
      (node (ref "C13") (pin "3") (pinfunction "3_3") (pintype "passive"))
      (node (ref "C4") (pin "1") (pinfunction "1_1") (pintype "passive"))
      (node (ref "LED1") (pin "1") (pinfunction "A_1") (pintype "passive"))
      (node (ref "LED4") (pin "1") (pinfunction "A_1") (pintype "passive"))
      (node (ref "LED6") (pin "1") (pinfunction "A_1") (pintype "passive"))
      (node (ref "LED8") (pin "1") (pinfunction "A_1") (pintype "passive"))
      (node (ref "LED9") (pin "1") (pinfunction "A_1") (pintype "passive"))
      (node (ref "R1") (pin "2") (pinfunction "2_2") (pintype "passive"))
      (node (ref "R13") (pin "2") (pinfunction "2_2") (pintype "passive"))
      (node (ref "R22") (pin "2") (pinfunction "2_2") (pintype "passive"))
      (node (ref "R25") (pin "2") (pinfunction "2_2") (pintype "passive"))
      (node (ref "R9") (pin "2") (pinfunction "2_2") (pintype "passive"))
      (node (ref "U7") (pin "15") (pinfunction "VIN_15") (pintype "passive"))
    )
    (net (code "61") (name "VCC12") (class "Default")
      (node (ref "BUCK LM1") (pin "1") (pinfunction "IN+_1") (pintype "passive"))
      (node (ref "C2") (pin "2") (pinfunction "2_2") (pintype "passive"))
    )
    (net (code "62") (name "VCC33_ISO") (class "Default")
      (node (ref "C8") (pin "1") (pinfunction "1_1") (pintype "passive"))
      (node (ref "U7") (pin "16") (pinfunction "3V3_16") (pintype "passive"))
    )
    (net (code "63") (name "unconnected-(C8-Pad3)") (class "Default")
      (node (ref "C8") (pin "3") (pinfunction "3_3") (pintype "passive+no_connect"))
    )
    (net (code "64") (name "unconnected-(RL1-Pad2)") (class "Default")
      (node (ref "RL1") (pin "2") (pinfunction "2_2") (pintype "passive+no_connect"))
    )
    (net (code "65") (name "unconnected-(RL2-Pad2)") (class "Default")
      (node (ref "RL2") (pin "2") (pinfunction "2_2") (pintype "passive+no_connect"))
    )
    (net (code "66") (name "unconnected-(RL3-Pad2)") (class "Default")
      (node (ref "RL3") (pin "2") (pinfunction "2_2") (pintype "passive+no_connect"))
    )
    (net (code "67") (name "unconnected-(RL4-Pad2)") (class "Default")
      (node (ref "RL4") (pin "2") (pinfunction "2_2") (pintype "passive+no_connect"))
    )
    (net (code "68") (name "unconnected-(U7-D2-Pad19)") (class "Default")
      (node (ref "U7") (pin "19") (pinfunction "D2_19") (pintype "passive+no_connect"))
    )
    (net (code "69") (name "unconnected-(U7-D12-Pad12)") (class "Default")
      (node (ref "U7") (pin "12") (pinfunction "D12_12") (pintype "passive+no_connect"))
    )
    (net (code "70") (name "unconnected-(U7-D23-Pad30)") (class "Default")
      (node (ref "U7") (pin "30") (pinfunction "D23_30") (pintype "passive"))
    )
    (net (code "71") (name "unconnected-(U7-D32-Pad6)") (class "Default")
      (node (ref "U7") (pin "6") (pinfunction "D32_6") (pintype "passive+no_connect"))
    )
    (net (code "72") (name "unconnected-(U7-D34-Pad4)") (class "Default")
      (node (ref "U7") (pin "4") (pinfunction "D34_4") (pintype "passive+no_connect"))
    )
    (net (code "73") (name "unconnected-(U7-D35-Pad5)") (class "Default")
      (node (ref "U7") (pin "5") (pinfunction "D35_5") (pintype "passive+no_connect"))
    )
    (net (code "74") (name "unconnected-(U7-EN-Pad1)") (class "Default")
      (node (ref "U7") (pin "1") (pinfunction "EN_1") (pintype "passive+no_connect"))
    )
    (net (code "75") (name "unconnected-(U7-RX0-Pad27)") (class "Default")
      (node (ref "U7") (pin "27") (pinfunction "RX0_27") (pintype "passive+no_connect"))
    )
    (net (code "76") (name "unconnected-(U7-RX2-Pad21)") (class "Default")
      (node (ref "U7") (pin "21") (pinfunction "RX2_21") (pintype "passive+no_connect"))
    )
    (net (code "77") (name "unconnected-(U7-TX0-Pad28)") (class "Default")
      (node (ref "U7") (pin "28") (pinfunction "TX0_28") (pintype "passive+no_connect"))
    )
    (net (code "78") (name "unconnected-(U7-TX2-Pad22)") (class "Default")
      (node (ref "U7") (pin "22") (pinfunction "TX2_22") (pintype "passive+no_connect"))
    )
    (net (code "79") (name "unconnected-(U7-VN-Pad3)") (class "Default")
      (node (ref "U7") (pin "3") (pinfunction "VN_3") (pintype "passive+no_connect"))
    )
  )
)
